# SCH_Light_Matrix_2024-06-19.net
KiCad netlist of a schematic drawn in EasyEDA
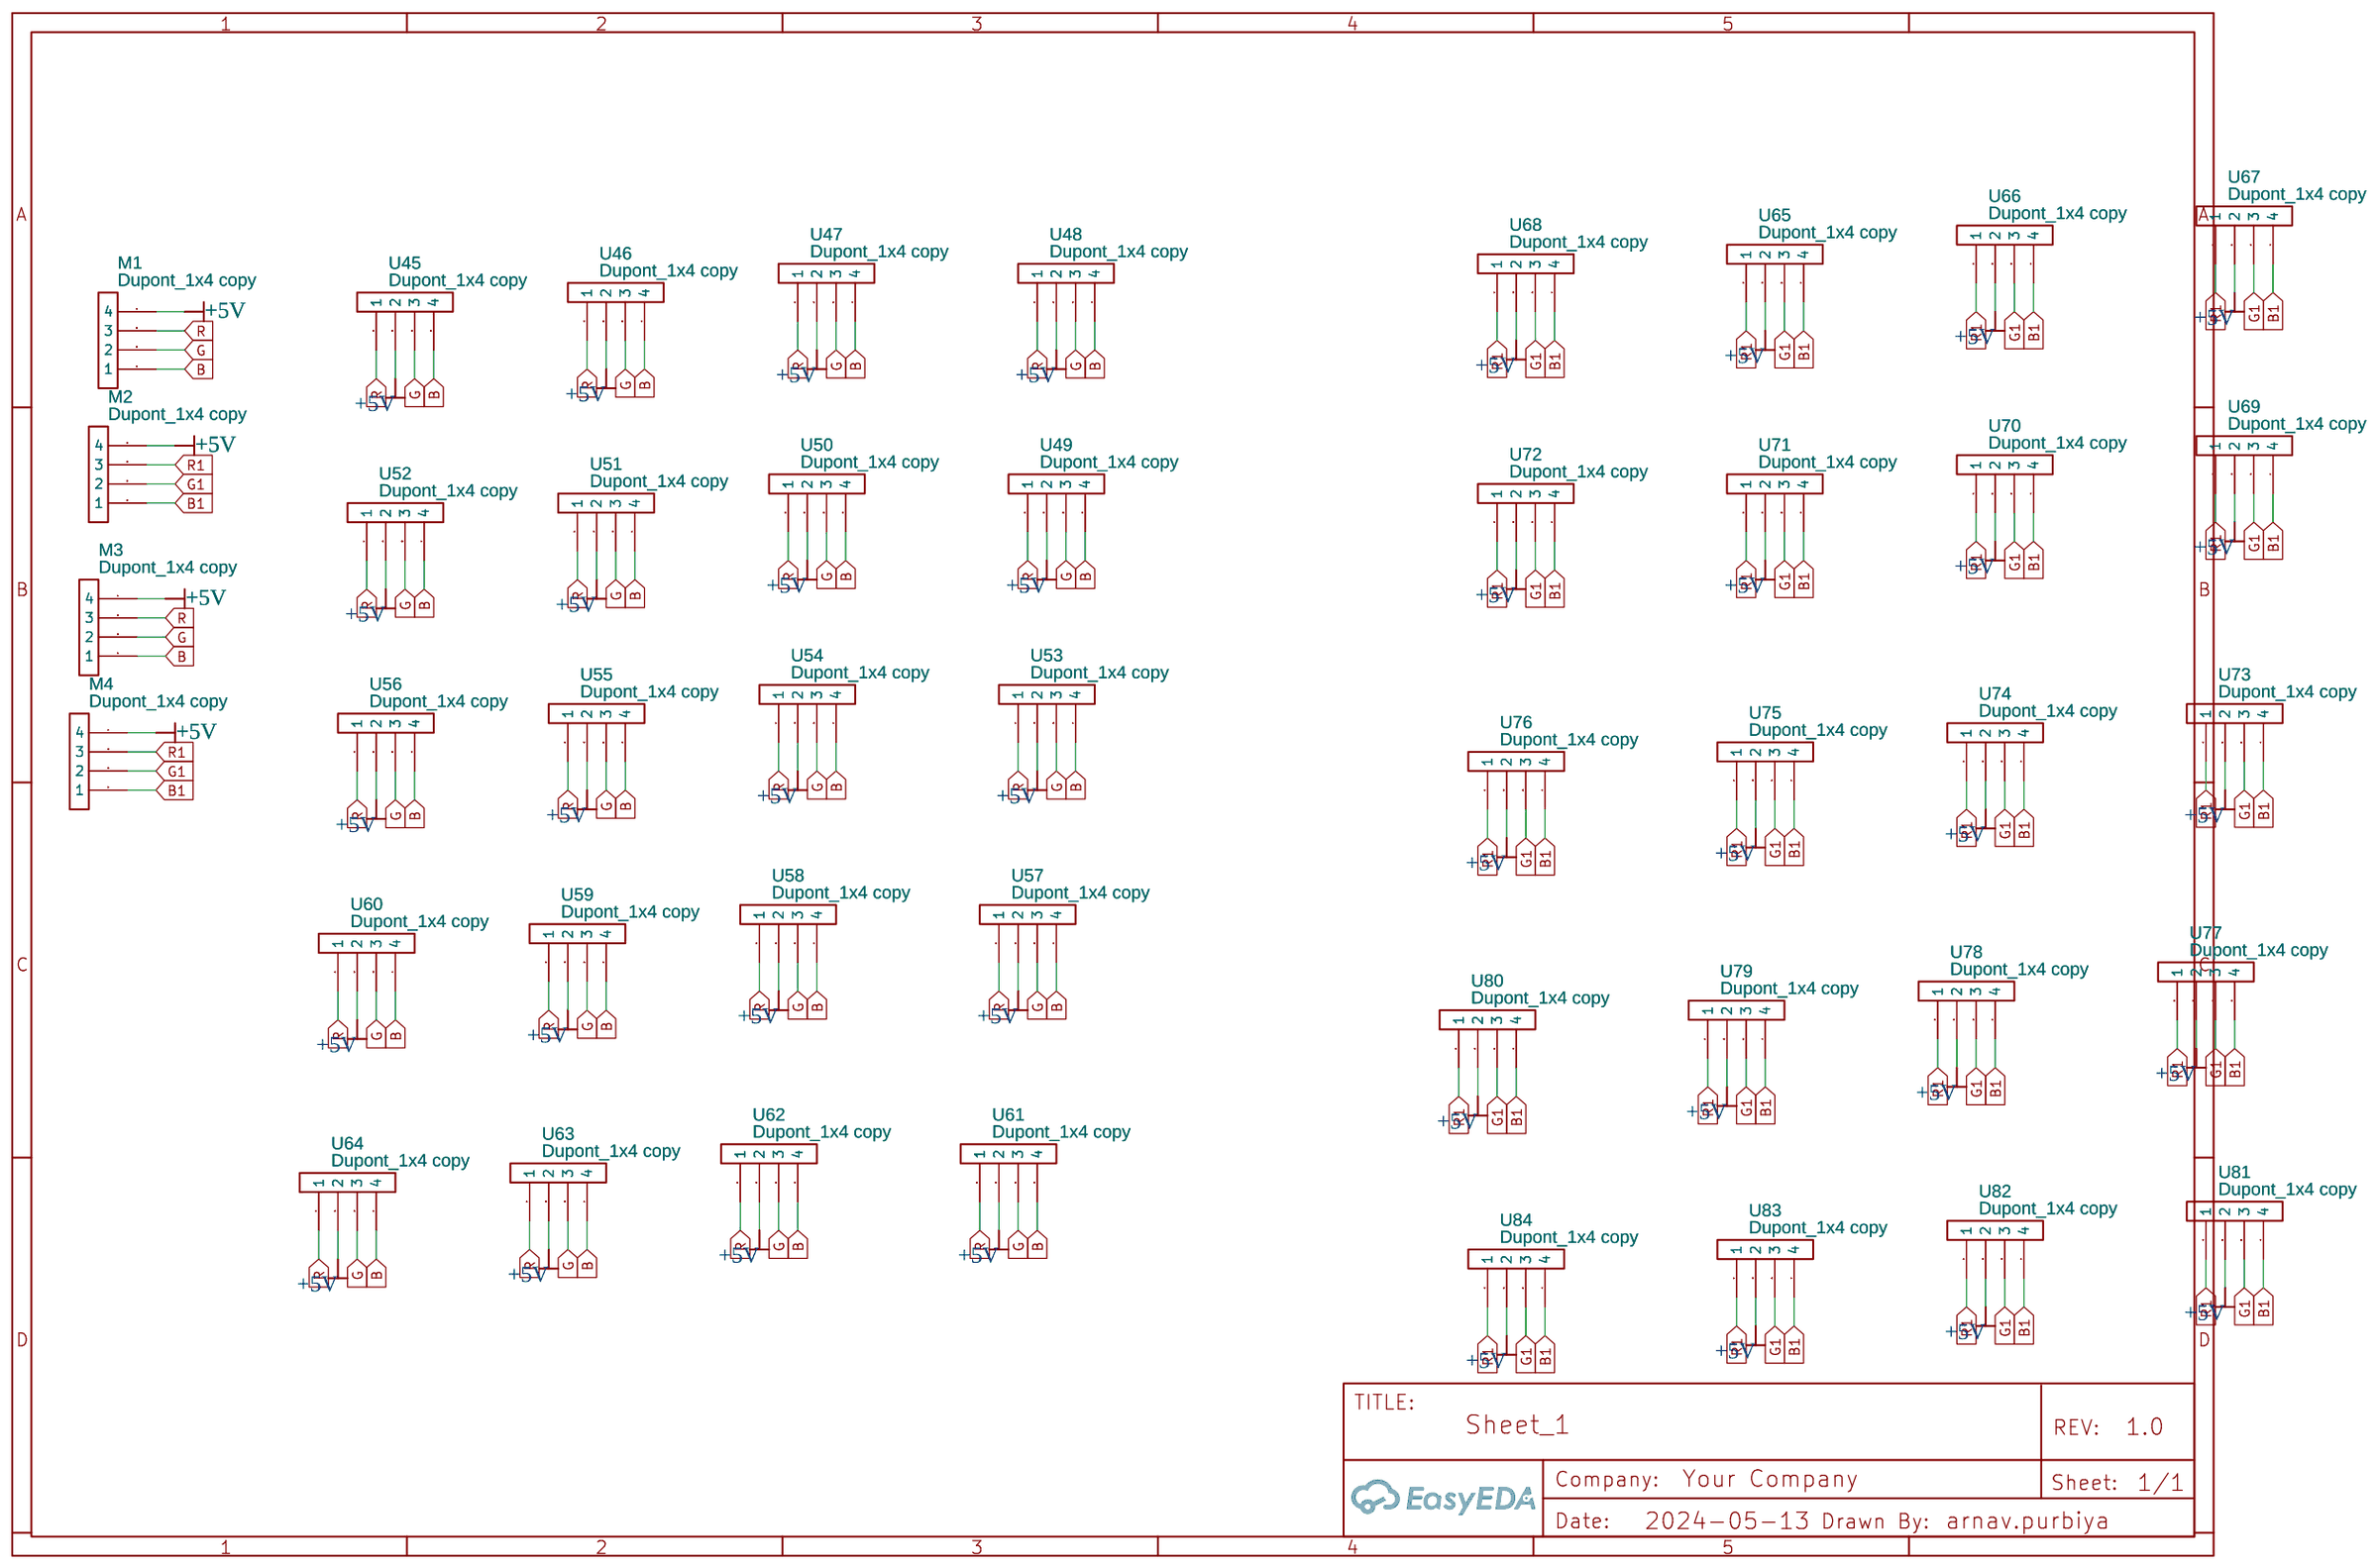
[diagram p0: schematic sheet]

(export (version "E")
  (design (tool "Eeschema 10.0.6"))
  (components
    (comp (ref "M1")
      (value "Dupont_1x4 copy")
      (fields (field (name "Manufacturer Part") "Conector_dupont"))
      (libsource (lib "") (part "Dupont_1x4 copy_1"))
    )
    (comp (ref "M2")
      (value "Dupont_1x4 copy")
      (fields (field (name "Manufacturer Part") "Conector_dupont"))
      (libsource (lib "") (part "Dupont_1x4 copy_1"))
    )
    (comp (ref "M3")
      (value "Dupont_1x4 copy")
      (fields (field (name "Manufacturer Part") "Conector_dupont"))
      (libsource (lib "") (part "Dupont_1x4 copy_1"))
    )
    (comp (ref "M4")
      (value "Dupont_1x4 copy")
      (fields (field (name "Manufacturer Part") "Conector_dupont"))
      (libsource (lib "") (part "Dupont_1x4 copy_1"))
    )
    (comp (ref "U45")
      (value "Dupont_1x4 copy")
      (fields (field (name "Manufacturer Part") "Conector_dupont"))
      (libsource (lib "") (part "Dupont_1x4 copy"))
    )
    (comp (ref "U46")
      (value "Dupont_1x4 copy")
      (fields (field (name "Manufacturer Part") "Conector_dupont"))
      (libsource (lib "") (part "Dupont_1x4 copy"))
    )
    (comp (ref "U47")
      (value "Dupont_1x4 copy")
      (fields (field (name "Manufacturer Part") "Conector_dupont"))
      (libsource (lib "") (part "Dupont_1x4 copy"))
    )
    (comp (ref "U48")
      (value "Dupont_1x4 copy")
      (fields (field (name "Manufacturer Part") "Conector_dupont"))
      (libsource (lib "") (part "Dupont_1x4 copy"))
    )
    (comp (ref "U49")
      (value "Dupont_1x4 copy")
      (fields (field (name "Manufacturer Part") "Conector_dupont"))
      (libsource (lib "") (part "Dupont_1x4 copy"))
    )
    (comp (ref "U50")
      (value "Dupont_1x4 copy")
      (fields (field (name "Manufacturer Part") "Conector_dupont"))
      (libsource (lib "") (part "Dupont_1x4 copy"))
    )
    (comp (ref "U51")
      (value "Dupont_1x4 copy")
      (fields (field (name "Manufacturer Part") "Conector_dupont"))
      (libsource (lib "") (part "Dupont_1x4 copy"))
    )
    (comp (ref "U52")
      (value "Dupont_1x4 copy")
      (fields (field (name "Manufacturer Part") "Conector_dupont"))
      (libsource (lib "") (part "Dupont_1x4 copy"))
    )
    (comp (ref "U53")
      (value "Dupont_1x4 copy")
      (fields (field (name "Manufacturer Part") "Conector_dupont"))
      (libsource (lib "") (part "Dupont_1x4 copy"))
    )
    (comp (ref "U54")
      (value "Dupont_1x4 copy")
      (fields (field (name "Manufacturer Part") "Conector_dupont"))
      (libsource (lib "") (part "Dupont_1x4 copy"))
    )
    (comp (ref "U55")
      (value "Dupont_1x4 copy")
      (fields (field (name "Manufacturer Part") "Conector_dupont"))
      (libsource (lib "") (part "Dupont_1x4 copy"))
    )
    (comp (ref "U56")
      (value "Dupont_1x4 copy")
      (fields (field (name "Manufacturer Part") "Conector_dupont"))
      (libsource (lib "") (part "Dupont_1x4 copy"))
    )
    (comp (ref "U57")
      (value "Dupont_1x4 copy")
      (fields (field (name "Manufacturer Part") "Conector_dupont"))
      (libsource (lib "") (part "Dupont_1x4 copy"))
    )
    (comp (ref "U58")
      (value "Dupont_1x4 copy")
      (fields (field (name "Manufacturer Part") "Conector_dupont"))
      (libsource (lib "") (part "Dupont_1x4 copy"))
    )
    (comp (ref "U59")
      (value "Dupont_1x4 copy")
      (fields (field (name "Manufacturer Part") "Conector_dupont"))
      (libsource (lib "") (part "Dupont_1x4 copy"))
    )
    (comp (ref "U60")
      (value "Dupont_1x4 copy")
      (fields (field (name "Manufacturer Part") "Conector_dupont"))
      (libsource (lib "") (part "Dupont_1x4 copy"))
    )
    (comp (ref "U61")
      (value "Dupont_1x4 copy")
      (fields (field (name "Manufacturer Part") "Conector_dupont"))
      (libsource (lib "") (part "Dupont_1x4 copy"))
    )
    (comp (ref "U62")
      (value "Dupont_1x4 copy")
      (fields (field (name "Manufacturer Part") "Conector_dupont"))
      (libsource (lib "") (part "Dupont_1x4 copy"))
    )
    (comp (ref "U63")
      (value "Dupont_1x4 copy")
      (fields (field (name "Manufacturer Part") "Conector_dupont"))
      (libsource (lib "") (part "Dupont_1x4 copy"))
    )
    (comp (ref "U64")
      (value "Dupont_1x4 copy")
      (fields (field (name "Manufacturer Part") "Conector_dupont"))
      (libsource (lib "") (part "Dupont_1x4 copy"))
    )
    (comp (ref "U65")
      (value "Dupont_1x4 copy")
      (fields (field (name "Manufacturer Part") "Conector_dupont"))
      (libsource (lib "") (part "Dupont_1x4 copy"))
    )
    (comp (ref "U66")
      (value "Dupont_1x4 copy")
      (fields (field (name "Manufacturer Part") "Conector_dupont"))
      (libsource (lib "") (part "Dupont_1x4 copy"))
    )
    (comp (ref "U67")
      (value "Dupont_1x4 copy")
      (fields (field (name "Manufacturer Part") "Conector_dupont"))
      (libsource (lib "") (part "Dupont_1x4 copy"))
    )
    (comp (ref "U68")
      (value "Dupont_1x4 copy")
      (fields (field (name "Manufacturer Part") "Conector_dupont"))
      (libsource (lib "") (part "Dupont_1x4 copy"))
    )
    (comp (ref "U69")
      (value "Dupont_1x4 copy")
      (fields (field (name "Manufacturer Part") "Conector_dupont"))
      (libsource (lib "") (part "Dupont_1x4 copy"))
    )
    (comp (ref "U70")
      (value "Dupont_1x4 copy")
      (fields (field (name "Manufacturer Part") "Conector_dupont"))
      (libsource (lib "") (part "Dupont_1x4 copy"))
    )
    (comp (ref "U71")
      (value "Dupont_1x4 copy")
      (fields (field (name "Manufacturer Part") "Conector_dupont"))
      (libsource (lib "") (part "Dupont_1x4 copy"))
    )
    (comp (ref "U72")
      (value "Dupont_1x4 copy")
      (fields (field (name "Manufacturer Part") "Conector_dupont"))
      (libsource (lib "") (part "Dupont_1x4 copy"))
    )
    (comp (ref "U73")
      (value "Dupont_1x4 copy")
      (fields (field (name "Manufacturer Part") "Conector_dupont"))
      (libsource (lib "") (part "Dupont_1x4 copy"))
    )
    (comp (ref "U74")
      (value "Dupont_1x4 copy")
      (fields (field (name "Manufacturer Part") "Conector_dupont"))
      (libsource (lib "") (part "Dupont_1x4 copy"))
    )
    (comp (ref "U75")
      (value "Dupont_1x4 copy")
      (fields (field (name "Manufacturer Part") "Conector_dupont"))
      (libsource (lib "") (part "Dupont_1x4 copy"))
    )
    (comp (ref "U76")
      (value "Dupont_1x4 copy")
      (fields (field (name "Manufacturer Part") "Conector_dupont"))
      (libsource (lib "") (part "Dupont_1x4 copy"))
    )
    (comp (ref "U77")
      (value "Dupont_1x4 copy")
      (fields (field (name "Manufacturer Part") "Conector_dupont"))
      (libsource (lib "") (part "Dupont_1x4 copy"))
    )
    (comp (ref "U78")
      (value "Dupont_1x4 copy")
      (fields (field (name "Manufacturer Part") "Conector_dupont"))
      (libsource (lib "") (part "Dupont_1x4 copy"))
    )
    (comp (ref "U79")
      (value "Dupont_1x4 copy")
      (fields (field (name "Manufacturer Part") "Conector_dupont"))
      (libsource (lib "") (part "Dupont_1x4 copy"))
    )
    (comp (ref "U80")
      (value "Dupont_1x4 copy")
      (fields (field (name "Manufacturer Part") "Conector_dupont"))
      (libsource (lib "") (part "Dupont_1x4 copy"))
    )
    (comp (ref "U81")
      (value "Dupont_1x4 copy")
      (fields (field (name "Manufacturer Part") "Conector_dupont"))
      (libsource (lib "") (part "Dupont_1x4 copy"))
    )
    (comp (ref "U82")
      (value "Dupont_1x4 copy")
      (fields (field (name "Manufacturer Part") "Conector_dupont"))
      (libsource (lib "") (part "Dupont_1x4 copy"))
    )
    (comp (ref "U83")
      (value "Dupont_1x4 copy")
      (fields (field (name "Manufacturer Part") "Conector_dupont"))
      (libsource (lib "") (part "Dupont_1x4 copy"))
    )
    (comp (ref "U84")
      (value "Dupont_1x4 copy")
      (fields (field (name "Manufacturer Part") "Conector_dupont"))
      (libsource (lib "") (part "Dupont_1x4 copy"))
    )
  )
  (nets
    (net (code "1") (name "+5V") (class "Default")
      (node (ref "M1") (pin "4") (pinfunction "4_4") (pintype "unspecified"))
      (node (ref "M2") (pin "4") (pinfunction "4_4") (pintype "unspecified"))
      (node (ref "M3") (pin "4") (pinfunction "4_4") (pintype "unspecified"))
      (node (ref "M4") (pin "4") (pinfunction "4_4") (pintype "unspecified"))
      (node (ref "U45") (pin "2") (pinfunction "2_2") (pintype "unspecified"))
      (node (ref "U46") (pin "2") (pinfunction "2_2") (pintype "unspecified"))
      (node (ref "U47") (pin "2") (pinfunction "2_2") (pintype "unspecified"))
      (node (ref "U48") (pin "2") (pinfunction "2_2") (pintype "unspecified"))
      (node (ref "U49") (pin "2") (pinfunction "2_2") (pintype "unspecified"))
      (node (ref "U50") (pin "2") (pinfunction "2_2") (pintype "unspecified"))
      (node (ref "U51") (pin "2") (pinfunction "2_2") (pintype "unspecified"))
      (node (ref "U52") (pin "2") (pinfunction "2_2") (pintype "unspecified"))
      (node (ref "U53") (pin "2") (pinfunction "2_2") (pintype "unspecified"))
      (node (ref "U54") (pin "2") (pinfunction "2_2") (pintype "unspecified"))
      (node (ref "U55") (pin "2") (pinfunction "2_2") (pintype "unspecified"))
      (node (ref "U56") (pin "2") (pinfunction "2_2") (pintype "unspecified"))
      (node (ref "U57") (pin "2") (pinfunction "2_2") (pintype "unspecified"))
      (node (ref "U58") (pin "2") (pinfunction "2_2") (pintype "unspecified"))
      (node (ref "U59") (pin "2") (pinfunction "2_2") (pintype "unspecified"))
      (node (ref "U60") (pin "2") (pinfunction "2_2") (pintype "unspecified"))
      (node (ref "U61") (pin "2") (pinfunction "2_2") (pintype "unspecified"))
      (node (ref "U62") (pin "2") (pinfunction "2_2") (pintype "unspecified"))
      (node (ref "U63") (pin "2") (pinfunction "2_2") (pintype "unspecified"))
      (node (ref "U64") (pin "2") (pinfunction "2_2") (pintype "unspecified"))
      (node (ref "U65") (pin "2") (pinfunction "2_2") (pintype "unspecified"))
      (node (ref "U66") (pin "2") (pinfunction "2_2") (pintype "unspecified"))
      (node (ref "U67") (pin "2") (pinfunction "2_2") (pintype "unspecified"))
      (node (ref "U68") (pin "2") (pinfunction "2_2") (pintype "unspecified"))
      (node (ref "U69") (pin "2") (pinfunction "2_2") (pintype "unspecified"))
      (node (ref "U70") (pin "2") (pinfunction "2_2") (pintype "unspecified"))
      (node (ref "U71") (pin "2") (pinfunction "2_2") (pintype "unspecified"))
      (node (ref "U72") (pin "2") (pinfunction "2_2") (pintype "unspecified"))
      (node (ref "U73") (pin "2") (pinfunction "2_2") (pintype "unspecified"))
      (node (ref "U74") (pin "2") (pinfunction "2_2") (pintype "unspecified"))
      (node (ref "U75") (pin "2") (pinfunction "2_2") (pintype "unspecified"))
      (node (ref "U76") (pin "2") (pinfunction "2_2") (pintype "unspecified"))
      (node (ref "U77") (pin "2") (pinfunction "2_2") (pintype "unspecified"))
      (node (ref "U78") (pin "2") (pinfunction "2_2") (pintype "unspecified"))
      (node (ref "U79") (pin "2") (pinfunction "2_2") (pintype "unspecified"))
      (node (ref "U80") (pin "2") (pinfunction "2_2") (pintype "unspecified"))
      (node (ref "U81") (pin "2") (pinfunction "2_2") (pintype "unspecified"))
      (node (ref "U82") (pin "2") (pinfunction "2_2") (pintype "unspecified"))
      (node (ref "U83") (pin "2") (pinfunction "2_2") (pintype "unspecified"))
      (node (ref "U84") (pin "2") (pinfunction "2_2") (pintype "unspecified"))
    )
    (net (code "2") (name "B") (class "Default")
      (node (ref "M1") (pin "1") (pinfunction "1_1") (pintype "unspecified"))
      (node (ref "M3") (pin "1") (pinfunction "1_1") (pintype "unspecified"))
      (node (ref "U45") (pin "4") (pinfunction "4_4") (pintype "unspecified"))
      (node (ref "U46") (pin "4") (pinfunction "4_4") (pintype "unspecified"))
      (node (ref "U47") (pin "4") (pinfunction "4_4") (pintype "unspecified"))
      (node (ref "U48") (pin "4") (pinfunction "4_4") (pintype "unspecified"))
      (node (ref "U49") (pin "4") (pinfunction "4_4") (pintype "unspecified"))
      (node (ref "U50") (pin "4") (pinfunction "4_4") (pintype "unspecified"))
      (node (ref "U51") (pin "4") (pinfunction "4_4") (pintype "unspecified"))
      (node (ref "U52") (pin "4") (pinfunction "4_4") (pintype "unspecified"))
      (node (ref "U53") (pin "4") (pinfunction "4_4") (pintype "unspecified"))
      (node (ref "U54") (pin "4") (pinfunction "4_4") (pintype "unspecified"))
      (node (ref "U55") (pin "4") (pinfunction "4_4") (pintype "unspecified"))
      (node (ref "U56") (pin "4") (pinfunction "4_4") (pintype "unspecified"))
      (node (ref "U57") (pin "4") (pinfunction "4_4") (pintype "unspecified"))
      (node (ref "U58") (pin "4") (pinfunction "4_4") (pintype "unspecified"))
      (node (ref "U59") (pin "4") (pinfunction "4_4") (pintype "unspecified"))
      (node (ref "U60") (pin "4") (pinfunction "4_4") (pintype "unspecified"))
      (node (ref "U61") (pin "4") (pinfunction "4_4") (pintype "unspecified"))
      (node (ref "U62") (pin "4") (pinfunction "4_4") (pintype "unspecified"))
      (node (ref "U63") (pin "4") (pinfunction "4_4") (pintype "unspecified"))
      (node (ref "U64") (pin "4") (pinfunction "4_4") (pintype "unspecified"))
    )
    (net (code "3") (name "B1") (class "Default")
      (node (ref "M2") (pin "1") (pinfunction "1_1") (pintype "unspecified"))
      (node (ref "M4") (pin "1") (pinfunction "1_1") (pintype "unspecified"))
      (node (ref "U65") (pin "4") (pinfunction "4_4") (pintype "unspecified"))
      (node (ref "U66") (pin "4") (pinfunction "4_4") (pintype "unspecified"))
      (node (ref "U67") (pin "4") (pinfunction "4_4") (pintype "unspecified"))
      (node (ref "U68") (pin "4") (pinfunction "4_4") (pintype "unspecified"))
      (node (ref "U69") (pin "4") (pinfunction "4_4") (pintype "unspecified"))
      (node (ref "U70") (pin "4") (pinfunction "4_4") (pintype "unspecified"))
      (node (ref "U71") (pin "4") (pinfunction "4_4") (pintype "unspecified"))
      (node (ref "U72") (pin "4") (pinfunction "4_4") (pintype "unspecified"))
      (node (ref "U73") (pin "4") (pinfunction "4_4") (pintype "unspecified"))
      (node (ref "U74") (pin "4") (pinfunction "4_4") (pintype "unspecified"))
      (node (ref "U75") (pin "4") (pinfunction "4_4") (pintype "unspecified"))
      (node (ref "U76") (pin "4") (pinfunction "4_4") (pintype "unspecified"))
      (node (ref "U77") (pin "4") (pinfunction "4_4") (pintype "unspecified"))
      (node (ref "U78") (pin "4") (pinfunction "4_4") (pintype "unspecified"))
      (node (ref "U79") (pin "4") (pinfunction "4_4") (pintype "unspecified"))
      (node (ref "U80") (pin "4") (pinfunction "4_4") (pintype "unspecified"))
      (node (ref "U81") (pin "4") (pinfunction "4_4") (pintype "unspecified"))
      (node (ref "U82") (pin "4") (pinfunction "4_4") (pintype "unspecified"))
      (node (ref "U83") (pin "4") (pinfunction "4_4") (pintype "unspecified"))
      (node (ref "U84") (pin "4") (pinfunction "4_4") (pintype "unspecified"))
    )
    (net (code "4") (name "G") (class "Default")
      (node (ref "M1") (pin "2") (pinfunction "2_2") (pintype "unspecified"))
      (node (ref "M3") (pin "2") (pinfunction "2_2") (pintype "unspecified"))
      (node (ref "U45") (pin "3") (pinfunction "3_3") (pintype "unspecified"))
      (node (ref "U46") (pin "3") (pinfunction "3_3") (pintype "unspecified"))
      (node (ref "U47") (pin "3") (pinfunction "3_3") (pintype "unspecified"))
      (node (ref "U48") (pin "3") (pinfunction "3_3") (pintype "unspecified"))
      (node (ref "U49") (pin "3") (pinfunction "3_3") (pintype "unspecified"))
      (node (ref "U50") (pin "3") (pinfunction "3_3") (pintype "unspecified"))
      (node (ref "U51") (pin "3") (pinfunction "3_3") (pintype "unspecified"))
      (node (ref "U52") (pin "3") (pinfunction "3_3") (pintype "unspecified"))
      (node (ref "U53") (pin "3") (pinfunction "3_3") (pintype "unspecified"))
      (node (ref "U54") (pin "3") (pinfunction "3_3") (pintype "unspecified"))
      (node (ref "U55") (pin "3") (pinfunction "3_3") (pintype "unspecified"))
      (node (ref "U56") (pin "3") (pinfunction "3_3") (pintype "unspecified"))
      (node (ref "U57") (pin "3") (pinfunction "3_3") (pintype "unspecified"))
      (node (ref "U58") (pin "3") (pinfunction "3_3") (pintype "unspecified"))
      (node (ref "U59") (pin "3") (pinfunction "3_3") (pintype "unspecified"))
      (node (ref "U60") (pin "3") (pinfunction "3_3") (pintype "unspecified"))
      (node (ref "U61") (pin "3") (pinfunction "3_3") (pintype "unspecified"))
      (node (ref "U62") (pin "3") (pinfunction "3_3") (pintype "unspecified"))
      (node (ref "U63") (pin "3") (pinfunction "3_3") (pintype "unspecified"))
      (node (ref "U64") (pin "3") (pinfunction "3_3") (pintype "unspecified"))
    )
    (net (code "5") (name "G1") (class "Default")
      (node (ref "M2") (pin "2") (pinfunction "2_2") (pintype "unspecified"))
      (node (ref "M4") (pin "2") (pinfunction "2_2") (pintype "unspecified"))
      (node (ref "U65") (pin "3") (pinfunction "3_3") (pintype "unspecified"))
      (node (ref "U66") (pin "3") (pinfunction "3_3") (pintype "unspecified"))
      (node (ref "U67") (pin "3") (pinfunction "3_3") (pintype "unspecified"))
      (node (ref "U68") (pin "3") (pinfunction "3_3") (pintype "unspecified"))
      (node (ref "U69") (pin "3") (pinfunction "3_3") (pintype "unspecified"))
      (node (ref "U70") (pin "3") (pinfunction "3_3") (pintype "unspecified"))
      (node (ref "U71") (pin "3") (pinfunction "3_3") (pintype "unspecified"))
      (node (ref "U72") (pin "3") (pinfunction "3_3") (pintype "unspecified"))
      (node (ref "U73") (pin "3") (pinfunction "3_3") (pintype "unspecified"))
      (node (ref "U74") (pin "3") (pinfunction "3_3") (pintype "unspecified"))
      (node (ref "U75") (pin "3") (pinfunction "3_3") (pintype "unspecified"))
      (node (ref "U76") (pin "3") (pinfunction "3_3") (pintype "unspecified"))
      (node (ref "U77") (pin "3") (pinfunction "3_3") (pintype "unspecified"))
      (node (ref "U78") (pin "3") (pinfunction "3_3") (pintype "unspecified"))
      (node (ref "U79") (pin "3") (pinfunction "3_3") (pintype "unspecified"))
      (node (ref "U80") (pin "3") (pinfunction "3_3") (pintype "unspecified"))
      (node (ref "U81") (pin "3") (pinfunction "3_3") (pintype "unspecified"))
      (node (ref "U82") (pin "3") (pinfunction "3_3") (pintype "unspecified"))
      (node (ref "U83") (pin "3") (pinfunction "3_3") (pintype "unspecified"))
      (node (ref "U84") (pin "3") (pinfunction "3_3") (pintype "unspecified"))
    )
    (net (code "6") (name "R") (class "Default")
      (node (ref "M1") (pin "3") (pinfunction "3_3") (pintype "unspecified"))
      (node (ref "M3") (pin "3") (pinfunction "3_3") (pintype "unspecified"))
      (node (ref "U45") (pin "1") (pinfunction "1_1") (pintype "unspecified"))
      (node (ref "U46") (pin "1") (pinfunction "1_1") (pintype "unspecified"))
      (node (ref "U47") (pin "1") (pinfunction "1_1") (pintype "unspecified"))
      (node (ref "U48") (pin "1") (pinfunction "1_1") (pintype "unspecified"))
      (node (ref "U49") (pin "1") (pinfunction "1_1") (pintype "unspecified"))
      (node (ref "U50") (pin "1") (pinfunction "1_1") (pintype "unspecified"))
      (node (ref "U51") (pin "1") (pinfunction "1_1") (pintype "unspecified"))
      (node (ref "U52") (pin "1") (pinfunction "1_1") (pintype "unspecified"))
      (node (ref "U53") (pin "1") (pinfunction "1_1") (pintype "unspecified"))
      (node (ref "U54") (pin "1") (pinfunction "1_1") (pintype "unspecified"))
      (node (ref "U55") (pin "1") (pinfunction "1_1") (pintype "unspecified"))
      (node (ref "U56") (pin "1") (pinfunction "1_1") (pintype "unspecified"))
      (node (ref "U57") (pin "1") (pinfunction "1_1") (pintype "unspecified"))
      (node (ref "U58") (pin "1") (pinfunction "1_1") (pintype "unspecified"))
      (node (ref "U59") (pin "1") (pinfunction "1_1") (pintype "unspecified"))
      (node (ref "U60") (pin "1") (pinfunction "1_1") (pintype "unspecified"))
      (node (ref "U61") (pin "1") (pinfunction "1_1") (pintype "unspecified"))
      (node (ref "U62") (pin "1") (pinfunction "1_1") (pintype "unspecified"))
      (node (ref "U63") (pin "1") (pinfunction "1_1") (pintype "unspecified"))
      (node (ref "U64") (pin "1") (pinfunction "1_1") (pintype "unspecified"))
    )
    (net (code "7") (name "R1") (class "Default")
      (node (ref "M2") (pin "3") (pinfunction "3_3") (pintype "unspecified"))
      (node (ref "M4") (pin "3") (pinfunction "3_3") (pintype "unspecified"))
      (node (ref "U65") (pin "1") (pinfunction "1_1") (pintype "unspecified"))
      (node (ref "U66") (pin "1") (pinfunction "1_1") (pintype "unspecified"))
      (node (ref "U67") (pin "1") (pinfunction "1_1") (pintype "unspecified"))
      (node (ref "U68") (pin "1") (pinfunction "1_1") (pintype "unspecified"))
      (node (ref "U69") (pin "1") (pinfunction "1_1") (pintype "unspecified"))
      (node (ref "U70") (pin "1") (pinfunction "1_1") (pintype "unspecified"))
      (node (ref "U71") (pin "1") (pinfunction "1_1") (pintype "unspecified"))
      (node (ref "U72") (pin "1") (pinfunction "1_1") (pintype "unspecified"))
      (node (ref "U73") (pin "1") (pinfunction "1_1") (pintype "unspecified"))
      (node (ref "U74") (pin "1") (pinfunction "1_1") (pintype "unspecified"))
      (node (ref "U75") (pin "1") (pinfunction "1_1") (pintype "unspecified"))
      (node (ref "U76") (pin "1") (pinfunction "1_1") (pintype "unspecified"))
      (node (ref "U77") (pin "1") (pinfunction "1_1") (pintype "unspecified"))
      (node (ref "U78") (pin "1") (pinfunction "1_1") (pintype "unspecified"))
      (node (ref "U79") (pin "1") (pinfunction "1_1") (pintype "unspecified"))
      (node (ref "U80") (pin "1") (pinfunction "1_1") (pintype "unspecified"))
      (node (ref "U81") (pin "1") (pinfunction "1_1") (pintype "unspecified"))
      (node (ref "U82") (pin "1") (pinfunction "1_1") (pintype "unspecified"))
      (node (ref "U83") (pin "1") (pinfunction "1_1") (pintype "unspecified"))
      (node (ref "U84") (pin "1") (pinfunction "1_1") (pintype "unspecified"))
    )
  )
)
